# clock.net
KiCad netlist of a schematic drawn in EAGLE
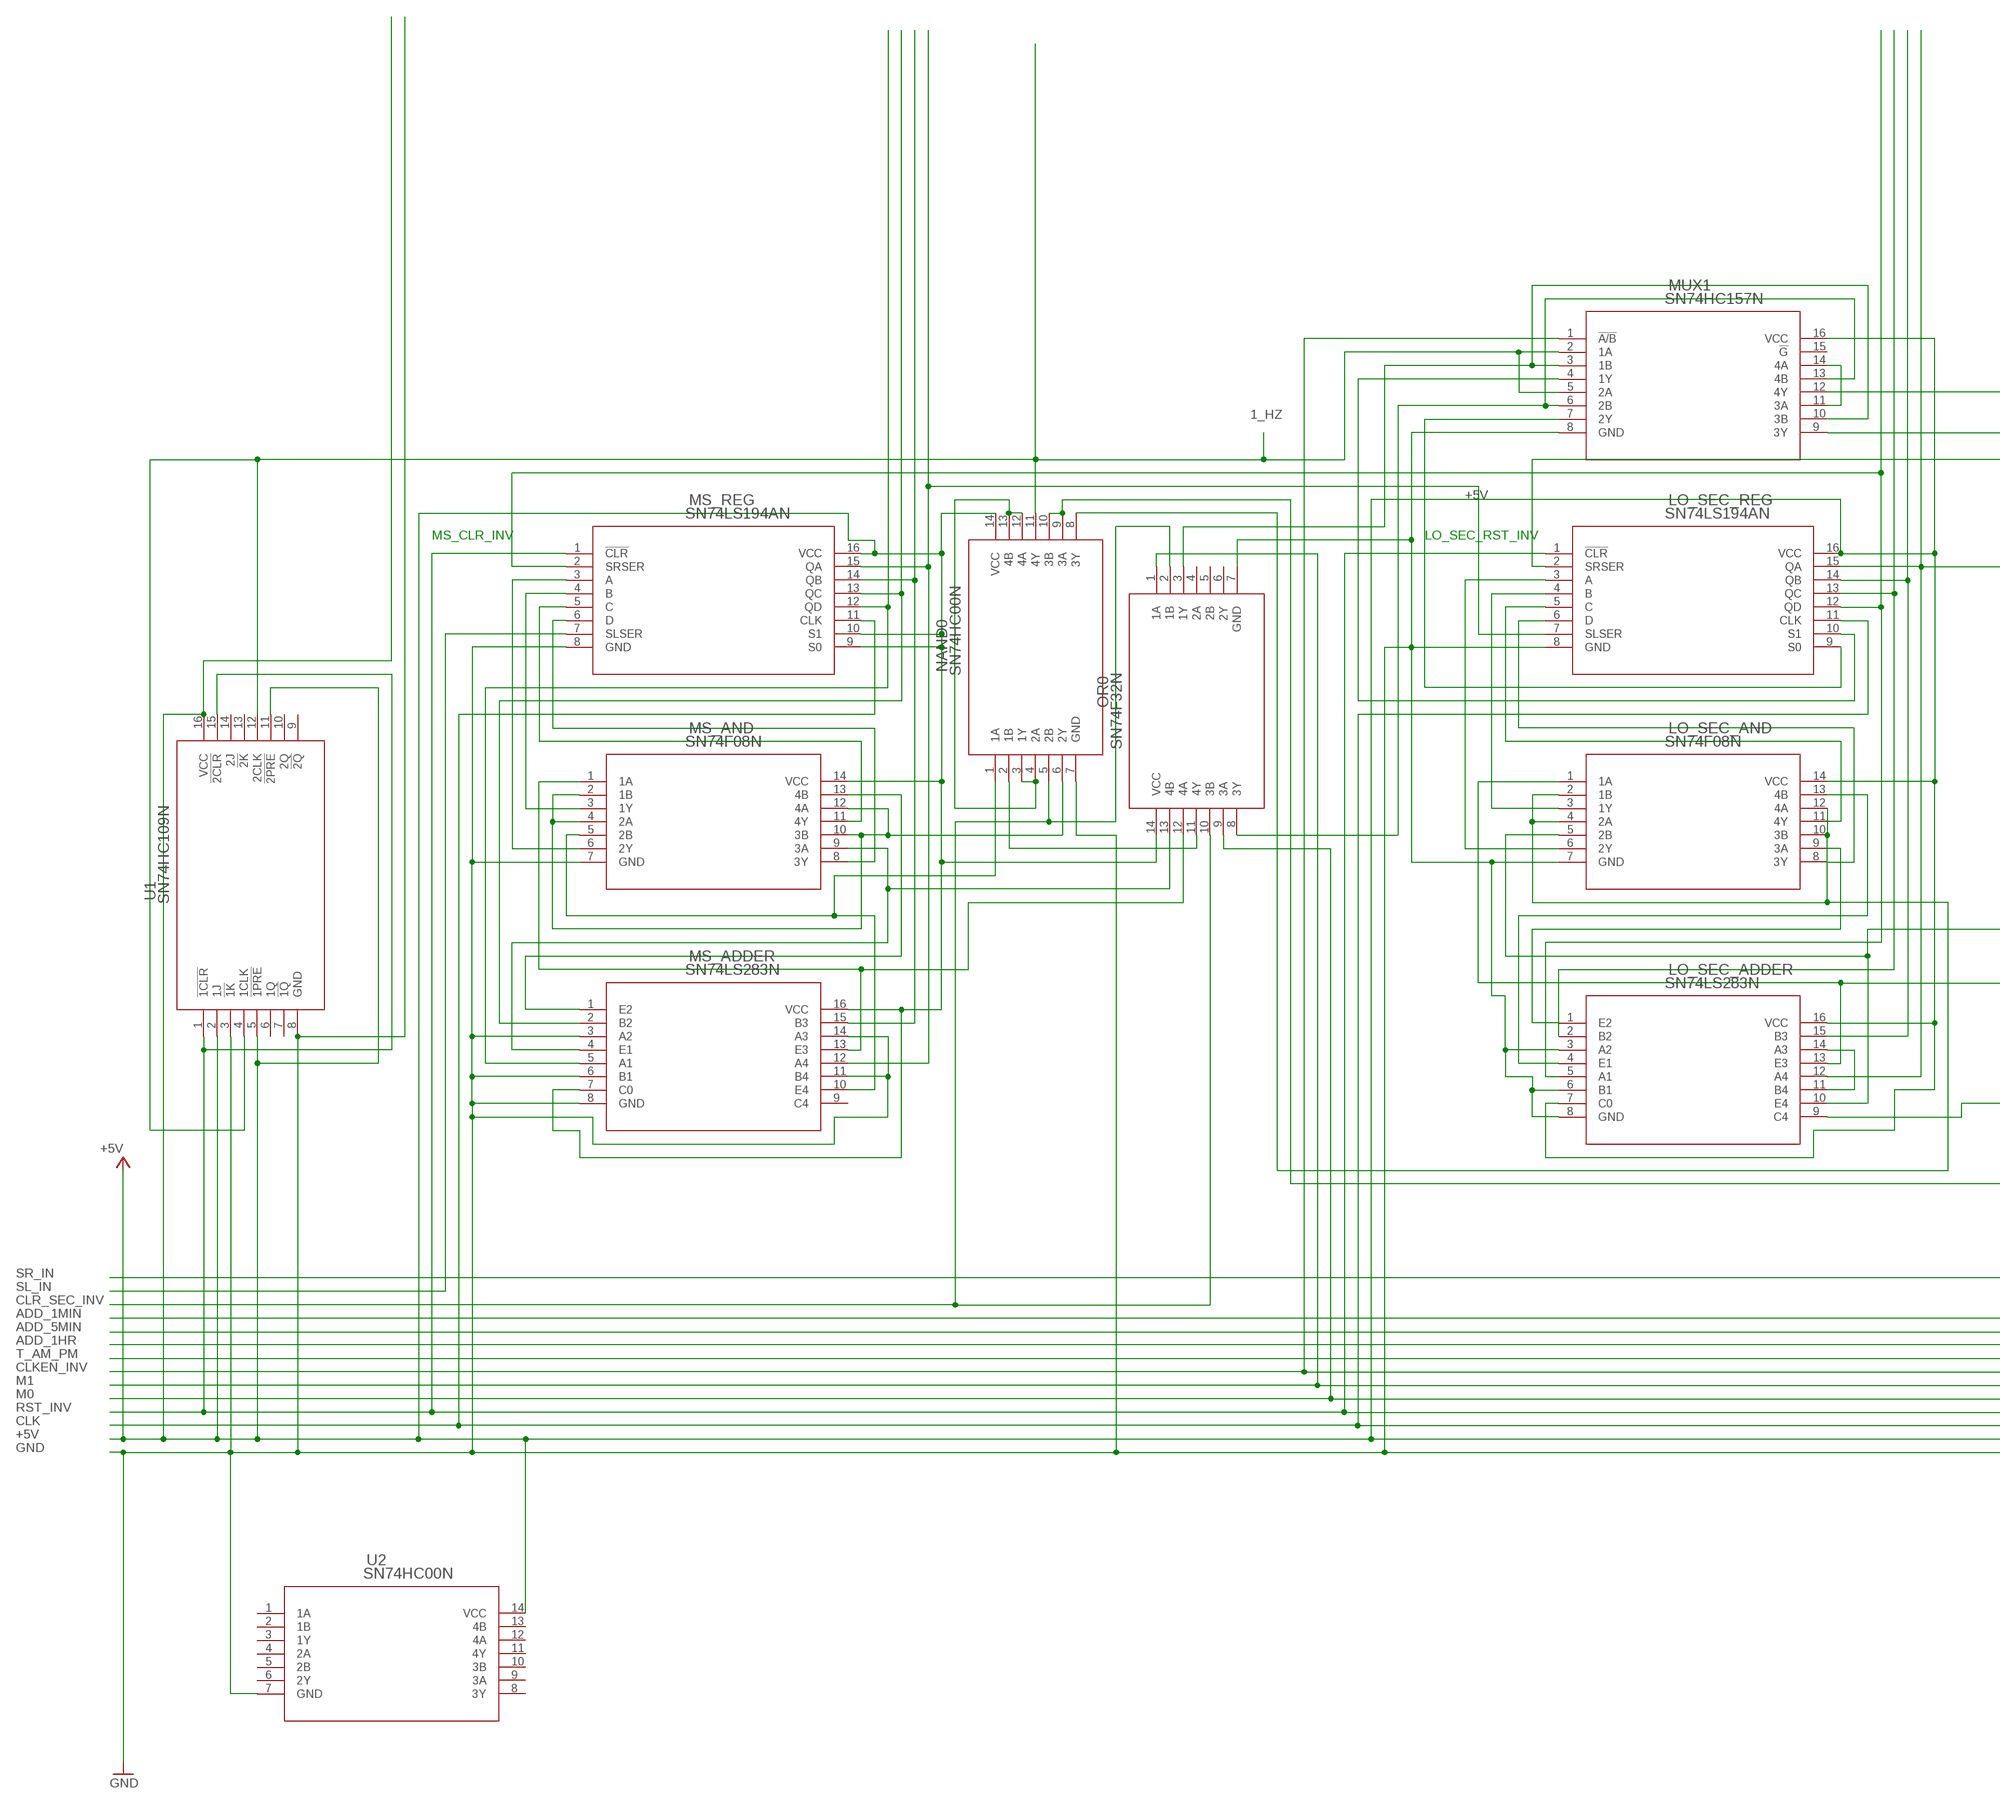
[diagram p0: schematic, sheet 1, part 1 of 3]
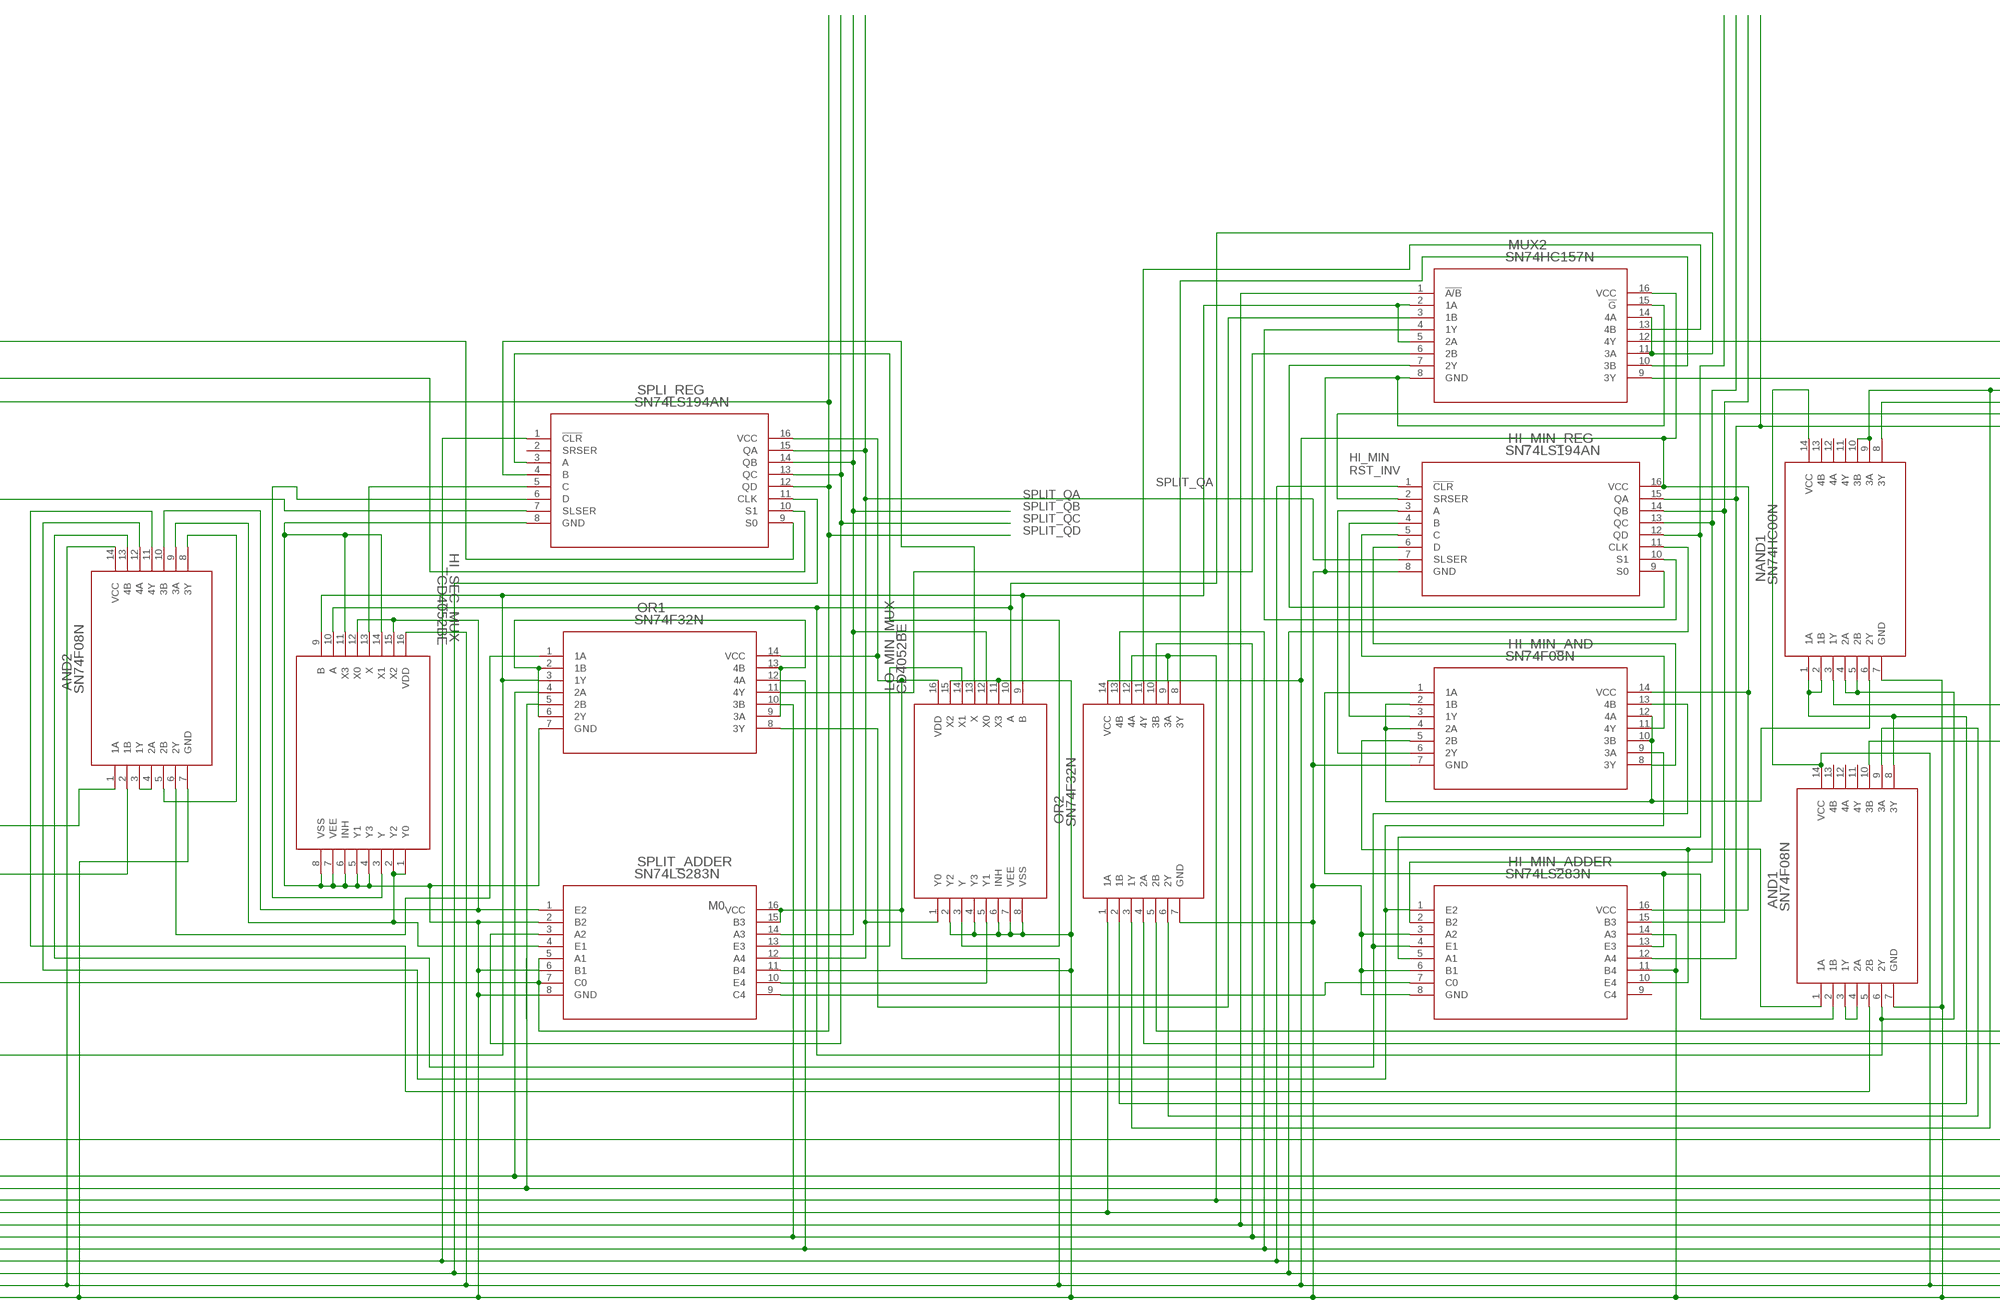
[diagram p1: schematic, sheet 1, part 2 of 3]
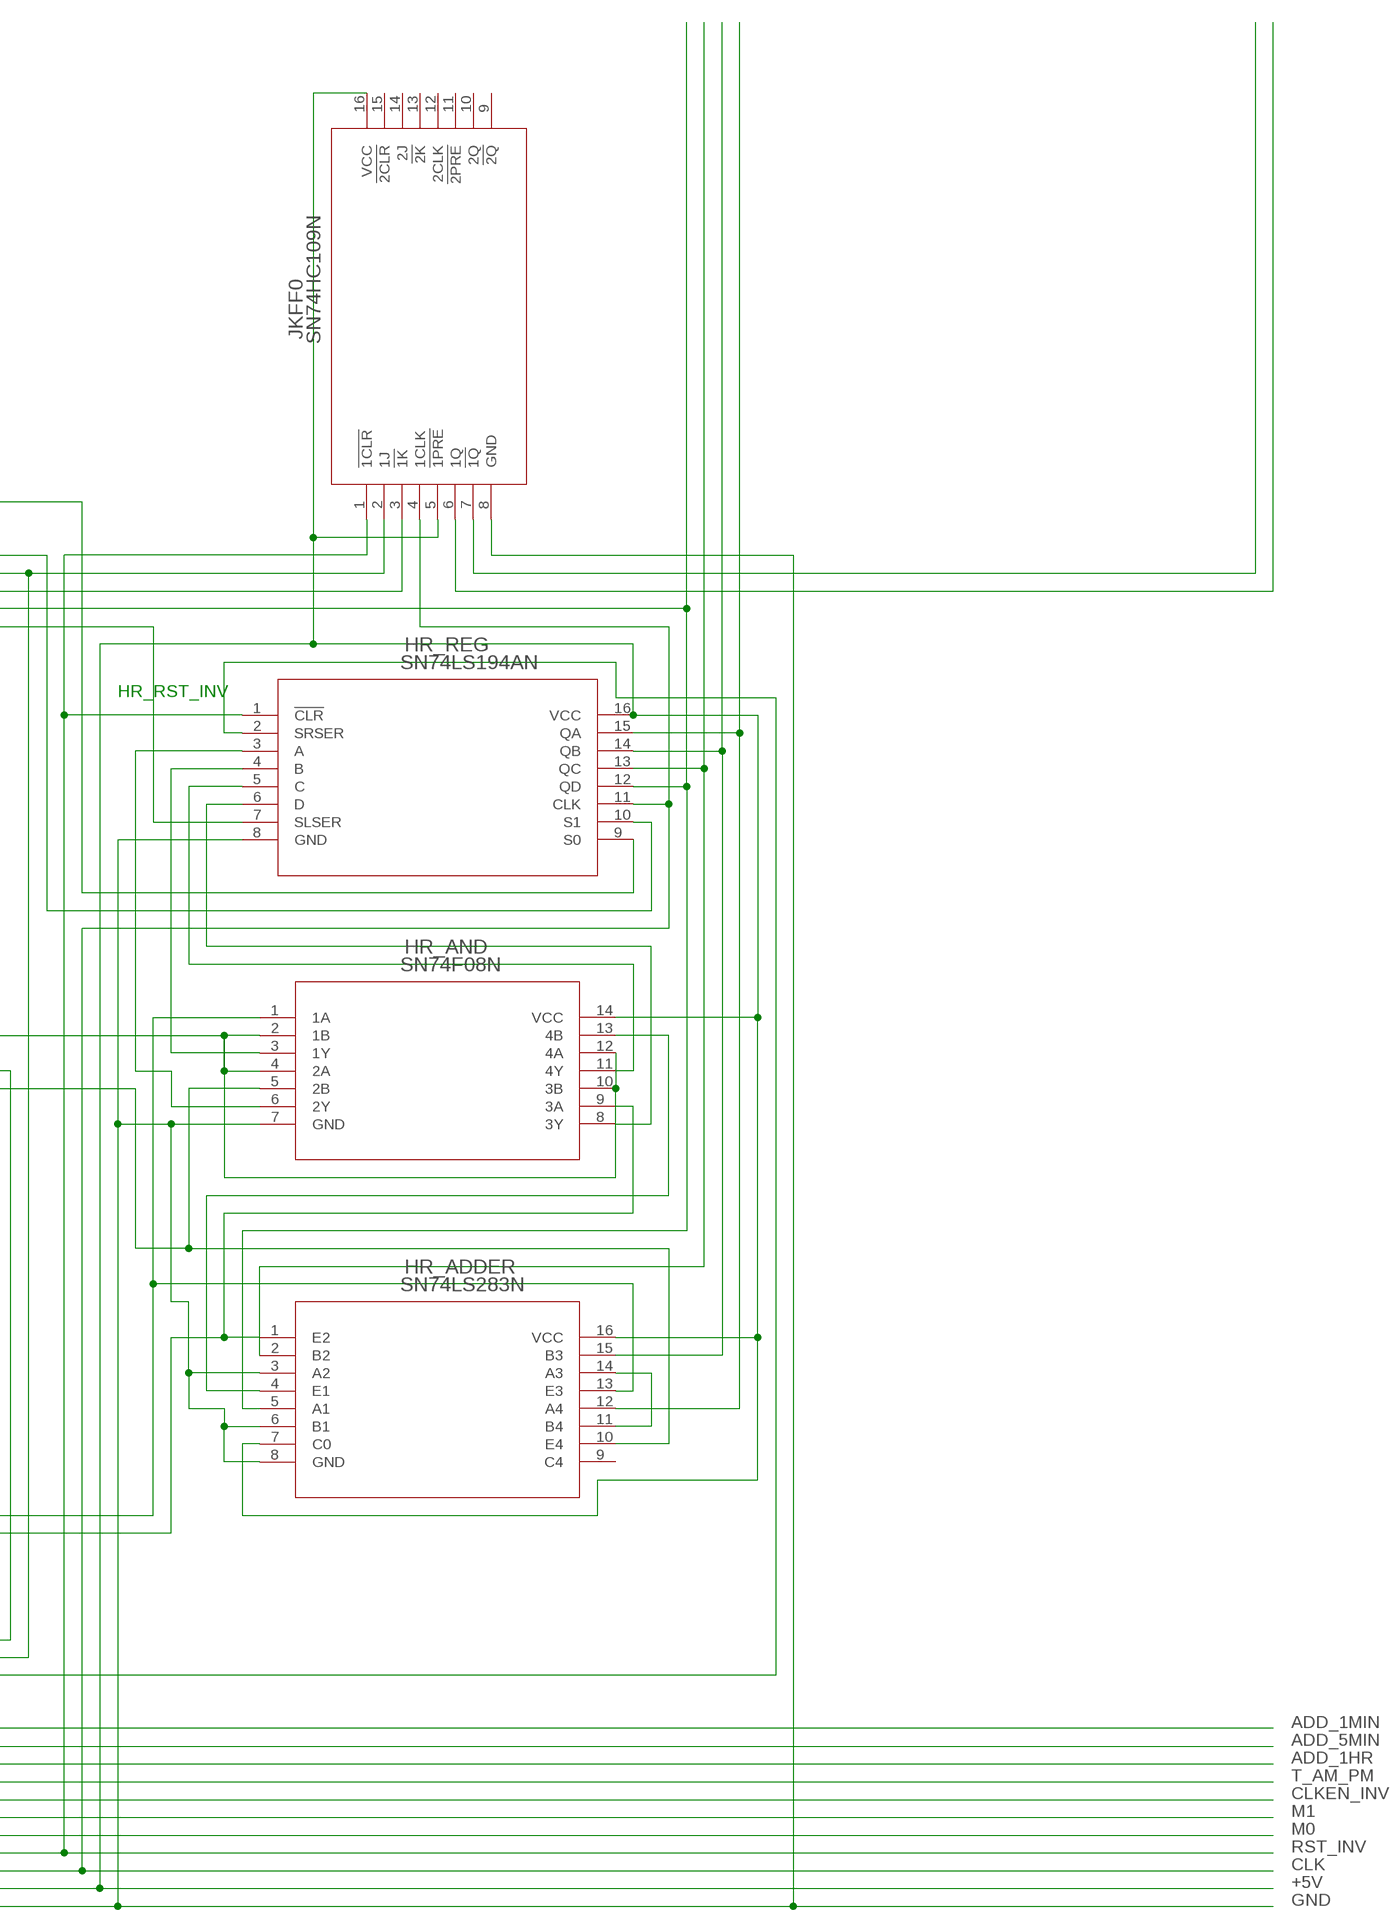
[diagram p2: schematic, sheet 1, part 3 of 3]

(export (version "E")
  (design (tool "Eeschema 10.0.6"))
  (components
    (comp (ref "AND1")
      (value "SN74F08N")
      (footprint "eagle-import:N14")
      (fields
        (field (name "GENERIC_PART_NUMBER") "SN74F08")
        (field (name "MANUFACTURER") "Texas Instruments")
      )
      (libsource (lib "eagle-import") (part "SN74F08N"))
    )
    (comp (ref "AND2")
      (value "SN74F08N")
      (footprint "eagle-import:N14")
      (fields
        (field (name "GENERIC_PART_NUMBER") "SN74F08")
        (field (name "MANUFACTURER") "Texas Instruments")
      )
      (libsource (lib "eagle-import") (part "SN74F08N"))
    )
    (comp (ref "HI_MIN_ADDER")
      (value "SN74LS283N")
      (footprint "eagle-import:N16")
      (fields
        (field (name "GENERIC_PART_NUMBER") "SN74LS283")
        (field (name "MANUFACTURER") "Texas Instruments")
      )
      (libsource (lib "eagle-import") (part "SN74LS283N"))
    )
    (comp (ref "HI_MIN_AND")
      (value "SN74F08N")
      (footprint "eagle-import:N14")
      (fields
        (field (name "GENERIC_PART_NUMBER") "SN74F08")
        (field (name "MANUFACTURER") "Texas Instruments")
      )
      (libsource (lib "eagle-import") (part "SN74F08N"))
    )
    (comp (ref "HI_MIN_REG")
      (value "SN74LS194AN")
      (footprint "eagle-import:N16")
      (fields
        (field (name "GENERIC_PART_NUMBER") "SN74LS194A")
        (field (name "MANUFACTURER") "Texas Instruments")
      )
      (libsource (lib "eagle-import") (part "SN74LS194AN"))
    )
    (comp (ref "HI_SEC_MUX")
      (value "CD4052BE")
      (footprint "eagle-import:N16")
      (fields
        (field (name "GENERIC_PART_NUMBER") "CD4052B")
        (field (name "MANUFACTURER") "Texas Instruments")
      )
      (libsource (lib "eagle-import") (part "CD4052BE"))
    )
    (comp (ref "HR_ADDER")
      (value "SN74LS283N")
      (footprint "eagle-import:N16")
      (fields
        (field (name "GENERIC_PART_NUMBER") "SN74LS283")
        (field (name "MANUFACTURER") "Texas Instruments")
      )
      (libsource (lib "eagle-import") (part "SN74LS283N"))
    )
    (comp (ref "HR_AND")
      (value "SN74F08N")
      (footprint "eagle-import:N14")
      (fields
        (field (name "GENERIC_PART_NUMBER") "SN74F08")
        (field (name "MANUFACTURER") "Texas Instruments")
      )
      (libsource (lib "eagle-import") (part "SN74F08N"))
    )
    (comp (ref "HR_REG")
      (value "SN74LS194AN")
      (footprint "eagle-import:N16")
      (fields
        (field (name "GENERIC_PART_NUMBER") "SN74LS194A")
        (field (name "MANUFACTURER") "Texas Instruments")
      )
      (libsource (lib "eagle-import") (part "SN74LS194AN"))
    )
    (comp (ref "JKFF0")
      (value "SN74HC109N")
      (footprint "eagle-import:N16")
      (fields
        (field (name "GENERIC_PART_NUMBER") "SN74HC109")
        (field (name "MANUFACTURER") "Texas Instruments")
      )
      (libsource (lib "eagle-import") (part "SN74HC109N"))
    )
    (comp (ref "LO_MIN_MUX")
      (value "CD4052BE")
      (footprint "eagle-import:N16")
      (fields
        (field (name "GENERIC_PART_NUMBER") "CD4052B")
        (field (name "MANUFACTURER") "Texas Instruments")
      )
      (libsource (lib "eagle-import") (part "CD4052BE"))
    )
    (comp (ref "LO_SEC_ADDER")
      (value "SN74LS283N")
      (footprint "eagle-import:N16")
      (fields
        (field (name "GENERIC_PART_NUMBER") "SN74LS283")
        (field (name "MANUFACTURER") "Texas Instruments")
      )
      (libsource (lib "eagle-import") (part "SN74LS283N"))
    )
    (comp (ref "LO_SEC_AND")
      (value "SN74F08N")
      (footprint "eagle-import:N14")
      (fields
        (field (name "GENERIC_PART_NUMBER") "SN74F08")
        (field (name "MANUFACTURER") "Texas Instruments")
      )
      (libsource (lib "eagle-import") (part "SN74F08N"))
    )
    (comp (ref "LO_SEC_REG")
      (value "SN74LS194AN")
      (footprint "eagle-import:N16")
      (fields
        (field (name "GENERIC_PART_NUMBER") "SN74LS194A")
        (field (name "MANUFACTURER") "Texas Instruments")
      )
      (libsource (lib "eagle-import") (part "SN74LS194AN"))
    )
    (comp (ref "MS_ADDER")
      (value "SN74LS283N")
      (footprint "eagle-import:N16")
      (fields
        (field (name "GENERIC_PART_NUMBER") "SN74LS283")
        (field (name "MANUFACTURER") "Texas Instruments")
      )
      (libsource (lib "eagle-import") (part "SN74LS283N"))
    )
    (comp (ref "MS_AND")
      (value "SN74F08N")
      (footprint "eagle-import:N14")
      (fields
        (field (name "GENERIC_PART_NUMBER") "SN74F08")
        (field (name "MANUFACTURER") "Texas Instruments")
      )
      (libsource (lib "eagle-import") (part "SN74F08N"))
    )
    (comp (ref "MS_REG")
      (value "SN74LS194AN")
      (footprint "eagle-import:N16")
      (fields
        (field (name "GENERIC_PART_NUMBER") "SN74LS194A")
        (field (name "MANUFACTURER") "Texas Instruments")
      )
      (libsource (lib "eagle-import") (part "SN74LS194AN"))
    )
    (comp (ref "MUX1")
      (value "SN74HC157N")
      (footprint "eagle-import:N16")
      (fields
        (field (name "GENERIC_PART_NUMBER") "SN74HC157")
        (field (name "MANUFACTURER") "Texas Instruments")
      )
      (libsource (lib "eagle-import") (part "SN74HC157N"))
    )
    (comp (ref "MUX2")
      (value "SN74HC157N")
      (footprint "eagle-import:N16")
      (fields
        (field (name "GENERIC_PART_NUMBER") "SN74HC157")
        (field (name "MANUFACTURER") "Texas Instruments")
      )
      (libsource (lib "eagle-import") (part "SN74HC157N"))
    )
    (comp (ref "NAND0")
      (value "SN74HC00N")
      (footprint "eagle-import:N14")
      (fields
        (field (name "GENERIC_PART_NUMBER") "SN74HC00")
        (field (name "MANUFACTURER") "Texas Instruments")
      )
      (libsource (lib "eagle-import") (part "SN74HC00N"))
    )
    (comp (ref "NAND1")
      (value "SN74HC00N")
      (footprint "eagle-import:N14")
      (fields
        (field (name "GENERIC_PART_NUMBER") "SN74HC00")
        (field (name "MANUFACTURER") "Texas Instruments")
      )
      (libsource (lib "eagle-import") (part "SN74HC00N"))
    )
    (comp (ref "OR0")
      (value "SN74F32N")
      (footprint "eagle-import:N14")
      (fields
        (field (name "GENERIC_PART_NUMBER") "SN74F32")
        (field (name "MANUFACTURER") "Texas Instruments")
      )
      (libsource (lib "eagle-import") (part "SN74F32N"))
    )
    (comp (ref "OR1")
      (value "SN74F32N")
      (footprint "eagle-import:N14")
      (fields
        (field (name "GENERIC_PART_NUMBER") "SN74F32")
        (field (name "MANUFACTURER") "Texas Instruments")
      )
      (libsource (lib "eagle-import") (part "SN74F32N"))
    )
    (comp (ref "OR2")
      (value "SN74F32N")
      (footprint "eagle-import:N14")
      (fields
        (field (name "GENERIC_PART_NUMBER") "SN74F32")
        (field (name "MANUFACTURER") "Texas Instruments")
      )
      (libsource (lib "eagle-import") (part "SN74F32N"))
    )
    (comp (ref "SPLIT_ADDER")
      (value "SN74LS283N")
      (footprint "eagle-import:N16")
      (fields
        (field (name "GENERIC_PART_NUMBER") "SN74LS283")
        (field (name "MANUFACTURER") "Texas Instruments")
      )
      (libsource (lib "eagle-import") (part "SN74LS283N"))
    )
    (comp (ref "SPLI_REG")
      (value "SN74LS194AN")
      (footprint "eagle-import:N16")
      (fields
        (field (name "GENERIC_PART_NUMBER") "SN74LS194A")
        (field (name "MANUFACTURER") "Texas Instruments")
      )
      (libsource (lib "eagle-import") (part "SN74LS194AN"))
    )
    (comp (ref "U1")
      (value "SN74HC109N")
      (footprint "eagle-import:N16")
      (fields
        (field (name "GENERIC_PART_NUMBER") "SN74HC109")
        (field (name "MANUFACTURER") "Texas Instruments")
      )
      (libsource (lib "eagle-import") (part "SN74HC109N"))
    )
    (comp (ref "U2")
      (value "SN74HC00N")
      (footprint "eagle-import:N14")
      (fields
        (field (name "GENERIC_PART_NUMBER") "SN74HC00")
        (field (name "MANUFACTURER") "Texas Instruments")
      )
      (libsource (lib "eagle-import") (part "SN74HC00N"))
    )
  )
  (nets
    (net (code "1") (name "+5V") (class "Default")
      (node (ref "AND1") (pin "14") (pinfunction "VCC_14") (pintype "power_in"))
      (node (ref "AND2") (pin "14") (pinfunction "VCC_14") (pintype "power_in"))
      (node (ref "HI_MIN_ADDER") (pin "16") (pinfunction "VCC_16") (pintype "power_in"))
      (node (ref "HI_MIN_AND") (pin "14") (pinfunction "VCC_14") (pintype "power_in"))
      (node (ref "HI_MIN_REG") (pin "16") (pinfunction "VCC_16") (pintype "power_in"))
      (node (ref "HI_SEC_MUX") (pin "16") (pinfunction "VDD_16") (pintype "power_in"))
      (node (ref "HR_ADDER") (pin "16") (pinfunction "VCC_16") (pintype "power_in"))
      (node (ref "HR_ADDER") (pin "7") (pinfunction "C0_7") (pintype "input"))
      (node (ref "HR_AND") (pin "14") (pinfunction "VCC_14") (pintype "power_in"))
      (node (ref "HR_REG") (pin "16") (pinfunction "VCC_16") (pintype "power_in"))
      (node (ref "JKFF0") (pin "16") (pinfunction "VCC_16") (pintype "power_in"))
      (node (ref "JKFF0") (pin "5") (pinfunction "~{1PRE}_5") (pintype "input"))
      (node (ref "LO_MIN_MUX") (pin "16") (pinfunction "VDD_16") (pintype "power_in"))
      (node (ref "LO_SEC_ADDER") (pin "16") (pinfunction "VCC_16") (pintype "power_in"))
      (node (ref "LO_SEC_ADDER") (pin "7") (pinfunction "C0_7") (pintype "input"))
      (node (ref "LO_SEC_AND") (pin "14") (pinfunction "VCC_14") (pintype "power_in"))
      (node (ref "LO_SEC_REG") (pin "16") (pinfunction "VCC_16") (pintype "power_in"))
      (node (ref "MS_ADDER") (pin "16") (pinfunction "VCC_16") (pintype "power_in"))
      (node (ref "MS_ADDER") (pin "7") (pinfunction "C0_7") (pintype "input"))
      (node (ref "MS_AND") (pin "14") (pinfunction "VCC_14") (pintype "power_in"))
      (node (ref "MS_REG") (pin "10") (pinfunction "S1_10") (pintype "input"))
      (node (ref "MS_REG") (pin "16") (pinfunction "VCC_16") (pintype "power_in"))
      (node (ref "MS_REG") (pin "9") (pinfunction "S0_9") (pintype "input"))
      (node (ref "MUX1") (pin "16") (pinfunction "VCC_16") (pintype "power_in"))
      (node (ref "MUX2") (pin "16") (pinfunction "VCC_16") (pintype "power_in"))
      (node (ref "NAND0") (pin "14") (pinfunction "VCC_14") (pintype "power_in"))
      (node (ref "NAND1") (pin "14") (pinfunction "VCC_14") (pintype "power_in"))
      (node (ref "OR0") (pin "14") (pinfunction "VCC_14") (pintype "power_in"))
      (node (ref "OR1") (pin "14") (pinfunction "VCC_14") (pintype "power_in"))
      (node (ref "OR2") (pin "14") (pinfunction "VCC_14") (pintype "power_in"))
      (node (ref "SPLIT_ADDER") (pin "15") (pinfunction "B3_15") (pintype "input"))
      (node (ref "SPLIT_ADDER") (pin "16") (pinfunction "VCC_16") (pintype "power_in"))
      (node (ref "SPLI_REG") (pin "16") (pinfunction "VCC_16") (pintype "power_in"))
      (node (ref "U1") (pin "11") (pinfunction "~{2PRE}_11") (pintype "input"))
      (node (ref "U1") (pin "16") (pinfunction "VCC_16") (pintype "power_in"))
      (node (ref "U1") (pin "2") (pinfunction "1J_2") (pintype "input"))
      (node (ref "U1") (pin "5") (pinfunction "~{1PRE}_5") (pintype "input"))
      (node (ref "U2") (pin "14") (pinfunction "VCC_14") (pintype "power_in"))
    )
    (net (code "2") (name "/1_HZ") (class "Default")
      (node (ref "MUX1") (pin "2") (pinfunction "1A_2") (pintype "input"))
      (node (ref "MUX1") (pin "5") (pinfunction "2A_5") (pintype "input"))
      (node (ref "NAND0") (pin "11") (pinfunction "4Y_11") (pintype "output"))
      (node (ref "U1") (pin "12") (pinfunction "2CLK_12") (pintype "input"))
      (node (ref "U1") (pin "4") (pinfunction "1CLK_4") (pintype "input"))
    )
    (net (code "3") (name "/ADD_1HR") (class "Default")
      (node (ref "OR2") (pin "12") (pinfunction "4A_12") (pintype "input"))
      (node (ref "OR2") (pin "9") (pinfunction "3A_9") (pintype "input"))
    )
    (net (code "4") (name "/ADD_1MIN") (class "Default")
      (node (ref "OR1") (pin "4") (pinfunction "2A_4") (pintype "input"))
    )
    (net (code "5") (name "/ADD_5MIN") (class "Default")
      (node (ref "OR1") (pin "5") (pinfunction "2B_5") (pintype "input"))
    )
    (net (code "6") (name "/CLK") (class "Default")
      (node (ref "HI_MIN_REG") (pin "11") (pinfunction "CLK_11") (pintype "input"))
      (node (ref "HR_REG") (pin "11") (pinfunction "CLK_11") (pintype "input"))
      (node (ref "JKFF0") (pin "4") (pinfunction "1CLK_4") (pintype "input"))
      (node (ref "LO_SEC_REG") (pin "11") (pinfunction "CLK_11") (pintype "input"))
      (node (ref "MS_REG") (pin "11") (pinfunction "CLK_11") (pintype "input"))
      (node (ref "SPLI_REG") (pin "11") (pinfunction "CLK_11") (pintype "input"))
    )
    (net (code "7") (name "/CLKEN_INV") (class "Default")
      (node (ref "MUX1") (pin "1") (pinfunction "~{A/B}_1") (pintype "input"))
      (node (ref "MUX2") (pin "1") (pinfunction "~{A/B}_1") (pintype "input"))
    )
    (net (code "8") (name "/CLR_SEC_INV") (class "Default")
      (node (ref "NAND0") (pin "5") (pinfunction "2B_5") (pintype "input"))
      (node (ref "OR0") (pin "10") (pinfunction "3B_10") (pintype "input"))
      (node (ref "OR0") (pin "2") (pinfunction "1B_2") (pintype "input"))
    )
    (net (code "9") (name "/M0") (class "Default")
      (node (ref "OR0") (pin "9") (pinfunction "3A_9") (pintype "input"))
      (node (ref "OR1") (pin "12") (pinfunction "4A_12") (pintype "input"))
      (node (ref "OR2") (pin "13") (pinfunction "4B_13") (pintype "input"))
    )
    (net (code "10") (name "/M1") (class "Default")
      (node (ref "OR0") (pin "1") (pinfunction "1A_1") (pintype "input"))
      (node (ref "OR1") (pin "10") (pinfunction "3B_10") (pintype "input"))
      (node (ref "OR2") (pin "10") (pinfunction "3B_10") (pintype "input"))
    )
    (net (code "11") (name "/RST_INV") (class "Default")
      (node (ref "HI_MIN_REG") (pin "1") (pinfunction "~{CLR}_1") (pintype "input"))
      (node (ref "HR_REG") (pin "1") (pinfunction "~{CLR}_1") (pintype "input"))
      (node (ref "JKFF0") (pin "1") (pinfunction "~{1CLR}_1") (pintype "input"))
      (node (ref "LO_SEC_REG") (pin "1") (pinfunction "~{CLR}_1") (pintype "input"))
      (node (ref "MS_REG") (pin "1") (pinfunction "~{CLR}_1") (pintype "input"))
      (node (ref "SPLI_REG") (pin "1") (pinfunction "~{CLR}_1") (pintype "input"))
      (node (ref "U1") (pin "1") (pinfunction "~{1CLR}_1") (pintype "input"))
      (node (ref "U1") (pin "15") (pinfunction "~{2CLR}_15") (pintype "input"))
    )
    (net (code "12") (name "/SL_IN") (class "Default")
      (node (ref "MS_REG") (pin "7") (pinfunction "SLSER_7") (pintype "input"))
    )
    (net (code "13") (name "/SPLIT_QA") (class "Default")
      (node (ref "HI_MIN_REG") (pin "7") (pinfunction "SLSER_7") (pintype "input"))
      (node (ref "LO_MIN_MUX") (pin "1") (pinfunction "Y0_1") (pintype "bidirectional"))
      (node (ref "SPLIT_ADDER") (pin "12") (pinfunction "A4_12") (pintype "input"))
      (node (ref "SPLI_REG") (pin "15") (pinfunction "QA_15") (pintype "output"))
    )
    (net (code "14") (name "/SPLIT_QB") (class "Default")
      (node (ref "LO_MIN_MUX") (pin "12") (pinfunction "X0_12") (pintype "bidirectional"))
      (node (ref "SPLIT_ADDER") (pin "14") (pinfunction "A3_14") (pintype "input"))
      (node (ref "SPLI_REG") (pin "14") (pinfunction "QB_14") (pintype "output"))
    )
    (net (code "15") (name "/SPLIT_QC") (class "Default")
      (node (ref "SPLIT_ADDER") (pin "3") (pinfunction "A2_3") (pintype "input"))
      (node (ref "SPLI_REG") (pin "13") (pinfunction "QC_13") (pintype "output"))
    )
    (net (code "16") (name "/SPLIT_QD") (class "Default")
      (node (ref "LO_SEC_ADDER") (pin "9") (pinfunction "C4_9") (pintype "input"))
      (node (ref "LO_SEC_REG") (pin "2") (pinfunction "SRSER_2") (pintype "input"))
      (node (ref "SPLIT_ADDER") (pin "5") (pinfunction "A1_5") (pintype "input"))
      (node (ref "SPLIT_ADDER") (pin "7") (pinfunction "C0_7") (pintype "input"))
      (node (ref "SPLI_REG") (pin "12") (pinfunction "QD_12") (pintype "output"))
    )
    (net (code "17") (name "/SR_IN") (class "Default")
      (node (ref "HR_REG") (pin "2") (pinfunction "SRSER_2") (pintype "input"))
    )
    (net (code "18") (name "/T_AM_PM") (class "Default")
      (node (ref "OR2") (pin "1") (pinfunction "1A_1") (pintype "input"))
    )
    (net (code "19") (name "GND") (class "Default")
      (node (ref "AND1") (pin "7") (pinfunction "GND_7") (pintype "power_in"))
      (node (ref "AND2") (pin "7") (pinfunction "GND_7") (pintype "power_in"))
      (node (ref "HI_MIN_ADDER") (pin "11") (pinfunction "B4_11") (pintype "input"))
      (node (ref "HI_MIN_ADDER") (pin "14") (pinfunction "A3_14") (pintype "input"))
      (node (ref "HI_MIN_ADDER") (pin "3") (pinfunction "A2_3") (pintype "input"))
      (node (ref "HI_MIN_ADDER") (pin "6") (pinfunction "B1_6") (pintype "input"))
      (node (ref "HI_MIN_ADDER") (pin "8") (pinfunction "GND_8") (pintype "power_in"))
      (node (ref "HI_MIN_AND") (pin "7") (pinfunction "GND_7") (pintype "power_in"))
      (node (ref "HI_MIN_REG") (pin "8") (pinfunction "GND_8") (pintype "power_in"))
      (node (ref "HI_SEC_MUX") (pin "11") (pinfunction "X3_11") (pintype "bidirectional"))
      (node (ref "HI_SEC_MUX") (pin "14") (pinfunction "X1_14") (pintype "bidirectional"))
      (node (ref "HI_SEC_MUX") (pin "4") (pinfunction "Y3_4") (pintype "bidirectional"))
      (node (ref "HI_SEC_MUX") (pin "5") (pinfunction "Y1_5") (pintype "bidirectional"))
      (node (ref "HI_SEC_MUX") (pin "6") (pinfunction "INH_6") (pintype "passive"))
      (node (ref "HI_SEC_MUX") (pin "7") (pinfunction "VEE_7") (pintype "power_in"))
      (node (ref "HI_SEC_MUX") (pin "8") (pinfunction "VSS_8") (pintype "power_in"))
      (node (ref "HR_ADDER") (pin "3") (pinfunction "A2_3") (pintype "input"))
      (node (ref "HR_ADDER") (pin "6") (pinfunction "B1_6") (pintype "input"))
      (node (ref "HR_ADDER") (pin "8") (pinfunction "GND_8") (pintype "power_in"))
      (node (ref "HR_AND") (pin "7") (pinfunction "GND_7") (pintype "power_in"))
      (node (ref "HR_REG") (pin "8") (pinfunction "GND_8") (pintype "power_in"))
      (node (ref "JKFF0") (pin "8") (pinfunction "GND_8") (pintype "power_in"))
      (node (ref "LO_MIN_MUX") (pin "11") (pinfunction "X3_11") (pintype "bidirectional"))
      (node (ref "LO_MIN_MUX") (pin "15") (pinfunction "X2_15") (pintype "bidirectional"))
      (node (ref "LO_MIN_MUX") (pin "2") (pinfunction "Y2_2") (pintype "bidirectional"))
      (node (ref "LO_MIN_MUX") (pin "4") (pinfunction "Y3_4") (pintype "bidirectional"))
      (node (ref "LO_MIN_MUX") (pin "6") (pinfunction "INH_6") (pintype "passive"))
      (node (ref "LO_MIN_MUX") (pin "7") (pinfunction "VEE_7") (pintype "power_in"))
      (node (ref "LO_MIN_MUX") (pin "8") (pinfunction "VSS_8") (pintype "power_in"))
      (node (ref "LO_SEC_ADDER") (pin "3") (pinfunction "A2_3") (pintype "input"))
      (node (ref "LO_SEC_ADDER") (pin "6") (pinfunction "B1_6") (pintype "input"))
      (node (ref "LO_SEC_ADDER") (pin "8") (pinfunction "GND_8") (pintype "power_in"))
      (node (ref "LO_SEC_AND") (pin "7") (pinfunction "GND_7") (pintype "power_in"))
      (node (ref "LO_SEC_REG") (pin "8") (pinfunction "GND_8") (pintype "power_in"))
      (node (ref "MS_ADDER") (pin "11") (pinfunction "B4_11") (pintype "input"))
      (node (ref "MS_ADDER") (pin "14") (pinfunction "A3_14") (pintype "input"))
      (node (ref "MS_ADDER") (pin "3") (pinfunction "A2_3") (pintype "input"))
      (node (ref "MS_ADDER") (pin "6") (pinfunction "B1_6") (pintype "input"))
      (node (ref "MS_ADDER") (pin "8") (pinfunction "GND_8") (pintype "power_in"))
      (node (ref "MS_AND") (pin "7") (pinfunction "GND_7") (pintype "power_in"))
      (node (ref "MS_REG") (pin "8") (pinfunction "GND_8") (pintype "power_in"))
      (node (ref "MUX1") (pin "8") (pinfunction "GND_8") (pintype "power_in"))
      (node (ref "MUX2") (pin "15") (pinfunction "~{G}_15") (pintype "input"))
      (node (ref "MUX2") (pin "8") (pinfunction "GND_8") (pintype "power_in"))
      (node (ref "NAND0") (pin "7") (pinfunction "GND_7") (pintype "power_in"))
      (node (ref "NAND1") (pin "7") (pinfunction "GND_7") (pintype "power_in"))
      (node (ref "OR0") (pin "7") (pinfunction "GND_7") (pintype "power_in"))
      (node (ref "OR1") (pin "7") (pinfunction "GND_7") (pintype "power_in"))
      (node (ref "OR2") (pin "7") (pinfunction "GND_7") (pintype "power_in"))
      (node (ref "SPLIT_ADDER") (pin "11") (pinfunction "B4_11") (pintype "input"))
      (node (ref "SPLIT_ADDER") (pin "2") (pinfunction "B2_2") (pintype "input"))
      (node (ref "SPLIT_ADDER") (pin "6") (pinfunction "B1_6") (pintype "input"))
      (node (ref "SPLIT_ADDER") (pin "8") (pinfunction "GND_8") (pintype "power_in"))
      (node (ref "SPLI_REG") (pin "8") (pinfunction "GND_8") (pintype "power_in"))
      (node (ref "U1") (pin "3") (pinfunction "~{1K}_3") (pintype "input"))
      (node (ref "U1") (pin "8") (pinfunction "GND_8") (pintype "power_in"))
      (node (ref "U2") (pin "7") (pinfunction "GND_7") (pintype "power_in"))
    )
    (net (code "20") (name "Net-(AND1-1A)") (class "Default")
      (node (ref "AND1") (pin "1") (pinfunction "1A_1") (pintype "input"))
      (node (ref "HI_MIN_ADDER") (pin "10") (pinfunction "E4_10") (pintype "output"))
      (node (ref "HI_MIN_AND") (pin "5") (pinfunction "2B_5") (pintype "input"))
    )
    (net (code "21") (name "Net-(AND1-1B)") (class "Default")
      (node (ref "AND1") (pin "2") (pinfunction "1B_2") (pintype "input"))
      (node (ref "HI_MIN_ADDER") (pin "13") (pinfunction "E3_13") (pintype "output"))
      (node (ref "HI_MIN_AND") (pin "1") (pinfunction "1A_1") (pintype "input"))
    )
    (net (code "22") (name "Net-(AND1-1Y)") (class "Default")
      (node (ref "AND1") (pin "3") (pinfunction "1Y_3") (pintype "output"))
      (node (ref "AND1") (pin "4") (pinfunction "2A_4") (pintype "input"))
    )
    (net (code "23") (name "Net-(AND1-2B)") (class "Default")
      (node (ref "AND1") (pin "5") (pinfunction "2B_5") (pintype "input"))
      (node (ref "AND2") (pin "11") (pinfunction "4Y_11") (pintype "output"))
    )
    (net (code "24") (name "Net-(AND1-2Y)") (class "Default")
      (node (ref "AND1") (pin "6") (pinfunction "2Y_6") (pintype "output"))
      (node (ref "HI_SEC_MUX") (pin "10") (pinfunction "A_10") (pintype "passive"))
      (node (ref "LO_MIN_MUX") (pin "10") (pinfunction "A_10") (pintype "passive"))
      (node (ref "MUX2") (pin "11") (pinfunction "3A_11") (pintype "input"))
      (node (ref "MUX2") (pin "14") (pinfunction "4A_14") (pintype "input"))
      (node (ref "NAND1") (pin "4") (pinfunction "2A_4") (pintype "input"))
      (node (ref "NAND1") (pin "5") (pinfunction "2B_5") (pintype "input"))
    )
    (net (code "25") (name "Net-(AND1-3A)") (class "Default")
      (node (ref "AND1") (pin "9") (pinfunction "3A_9") (pintype "input"))
      (node (ref "OR2") (pin "6") (pinfunction "2Y_6") (pintype "output"))
    )
    (net (code "26") (name "Net-(AND1-3B)") (class "Default")
      (node (ref "AND1") (pin "10") (pinfunction "3B_10") (pintype "input"))
      (node (ref "HR_ADDER") (pin "10") (pinfunction "E4_10") (pintype "output"))
      (node (ref "HR_AND") (pin "5") (pinfunction "2B_5") (pintype "input"))
    )
    (net (code "27") (name "Net-(AND1-3Y)") (class "Default")
      (node (ref "AND1") (pin "8") (pinfunction "3Y_8") (pintype "output"))
      (node (ref "NAND1") (pin "1") (pinfunction "1A_1") (pintype "input"))
      (node (ref "NAND1") (pin "2") (pinfunction "1B_2") (pintype "input"))
      (node (ref "OR2") (pin "2") (pinfunction "1B_2") (pintype "input"))
    )
    (net (code "28") (name "Net-(AND2-1A)") (class "Default")
      (node (ref "AND2") (pin "1") (pinfunction "1A_1") (pintype "input"))
      (node (ref "LO_SEC_ADDER") (pin "10") (pinfunction "E4_10") (pintype "output"))
      (node (ref "LO_SEC_AND") (pin "5") (pinfunction "2B_5") (pintype "input"))
    )
    (net (code "29") (name "Net-(AND2-1B)") (class "Default")
      (node (ref "AND2") (pin "2") (pinfunction "1B_2") (pintype "input"))
      (node (ref "LO_SEC_ADDER") (pin "13") (pinfunction "E3_13") (pintype "output"))
      (node (ref "LO_SEC_AND") (pin "1") (pinfunction "1A_1") (pintype "input"))
    )
    (net (code "30") (name "Net-(AND2-1Y)") (class "Default")
      (node (ref "AND2") (pin "3") (pinfunction "1Y_3") (pintype "output"))
      (node (ref "AND2") (pin "4") (pinfunction "2A_4") (pintype "input"))
    )
    (net (code "31") (name "Net-(AND2-2B)") (class "Default")
      (node (ref "AND2") (pin "5") (pinfunction "2B_5") (pintype "input"))
      (node (ref "AND2") (pin "8") (pinfunction "3Y_8") (pintype "output"))
    )
    (net (code "32") (name "Net-(AND2-2Y)") (class "Default")
      (node (ref "AND2") (pin "6") (pinfunction "2Y_6") (pintype "output"))
      (node (ref "OR1") (pin "1") (pinfunction "1A_1") (pintype "input"))
    )
    (net (code "33") (name "Net-(AND2-3A)") (class "Default")
      (node (ref "AND2") (pin "9") (pinfunction "3A_9") (pintype "input"))
      (node (ref "HI_SEC_MUX") (pin "1") (pinfunction "Y0_1") (pintype "bidirectional"))
      (node (ref "HI_SEC_MUX") (pin "2") (pinfunction "Y2_2") (pintype "bidirectional"))
      (node (ref "SPLIT_ADDER") (pin "4") (pinfunction "E1_4") (pintype "output"))
    )
    (net (code "34") (name "Net-(AND2-3B)") (class "Default")
      (node (ref "AND2") (pin "10") (pinfunction "3B_10") (pintype "input"))
      (node (ref "HI_SEC_MUX") (pin "12") (pinfunction "X0_12") (pintype "bidirectional"))
      (node (ref "HI_SEC_MUX") (pin "15") (pinfunction "X2_15") (pintype "bidirectional"))
      (node (ref "SPLIT_ADDER") (pin "1") (pinfunction "E2_1") (pintype "output"))
    )
    (net (code "35") (name "Net-(AND2-4A)") (class "Default")
      (node (ref "AND2") (pin "12") (pinfunction "4A_12") (pintype "input"))
      (node (ref "HI_MIN_ADDER") (pin "1") (pinfunction "E2_1") (pintype "output"))
      (node (ref "HI_MIN_AND") (pin "9") (pinfunction "3A_9") (pintype "input"))
    )
    (net (code "36") (name "Net-(AND2-4B)") (class "Default")
      (node (ref "AND2") (pin "13") (pinfunction "4B_13") (pintype "input"))
      (node (ref "HI_MIN_ADDER") (pin "4") (pinfunction "E1_4") (pintype "output"))
      (node (ref "HI_MIN_AND") (pin "13") (pinfunction "4B_13") (pintype "input"))
    )
    (net (code "37") (name "Net-(HI_MIN_ADDER-A1)") (class "Default")
      (node (ref "HI_MIN_ADDER") (pin "5") (pinfunction "A1_5") (pintype "input"))
      (node (ref "HI_MIN_REG") (pin "12") (pinfunction "QD_12") (pintype "output"))
    )
    (net (code "38") (name "Net-(HI_MIN_ADDER-A4)") (class "Default")
      (node (ref "HI_MIN_ADDER") (pin "12") (pinfunction "A4_12") (pintype "input"))
      (node (ref "HI_MIN_REG") (pin "15") (pinfunction "QA_15") (pintype "output"))
      (node (ref "HR_REG") (pin "7") (pinfunction "SLSER_7") (pintype "input"))
    )
    (net (code "39") (name "Net-(HI_MIN_ADDER-B2)") (class "Default")
      (node (ref "HI_MIN_ADDER") (pin "2") (pinfunction "B2_2") (pintype "input"))
      (node (ref "HI_MIN_REG") (pin "13") (pinfunction "QC_13") (pintype "output"))
    )
    (net (code "40") (name "Net-(HI_MIN_ADDER-B3)") (class "Default")
      (node (ref "HI_MIN_ADDER") (pin "15") (pinfunction "B3_15") (pintype "input"))
      (node (ref "HI_MIN_REG") (pin "14") (pinfunction "QB_14") (pintype "output"))
    )
    (net (code "41") (name "Net-(HI_MIN_ADDER-C0)") (class "Default")
      (node (ref "HI_MIN_ADDER") (pin "7") (pinfunction "C0_7") (pintype "input"))
      (node (ref "SPLIT_ADDER") (pin "9") (pinfunction "C4_9") (pintype "input"))
    )
    (net (code "42") (name "Net-(HI_MIN_AND-1B)") (class "Default")
      (node (ref "HI_MIN_AND") (pin "10") (pinfunction "3B_10") (pintype "input"))
      (node (ref "HI_MIN_AND") (pin "12") (pinfunction "4A_12") (pintype "input"))
      (node (ref "HI_MIN_AND") (pin "2") (pinfunction "1B_2") (pintype "input"))
      (node (ref "HI_MIN_AND") (pin "4") (pinfunction "2A_4") (pintype "input"))
      (node (ref "NAND1") (pin "6") (pinfunction "2Y_6") (pintype "output"))
    )
    (net (code "43") (name "Net-(HI_MIN_AND-1Y)") (class "Default")
      (node (ref "HI_MIN_AND") (pin "3") (pinfunction "1Y_3") (pintype "output"))
      (node (ref "HI_MIN_REG") (pin "4") (pinfunction "B_4") (pintype "input"))
    )
    (net (code "44") (name "Net-(HI_MIN_AND-2Y)") (class "Default")
      (node (ref "HI_MIN_AND") (pin "6") (pinfunction "2Y_6") (pintype "output"))
      (node (ref "HI_MIN_REG") (pin "3") (pinfunction "A_3") (pintype "input"))
    )
    (net (code "45") (name "Net-(HI_MIN_AND-3Y)") (class "Default")
      (node (ref "HI_MIN_AND") (pin "8") (pinfunction "3Y_8") (pintype "output"))
      (node (ref "HI_MIN_REG") (pin "6") (pinfunction "D_6") (pintype "input"))
    )
    (net (code "46") (name "Net-(HI_MIN_AND-4Y)") (class "Default")
      (node (ref "HI_MIN_AND") (pin "11") (pinfunction "4Y_11") (pintype "output"))
      (node (ref "HI_MIN_REG") (pin "5") (pinfunction "C_5") (pintype "input"))
    )
    (net (code "47") (name "Net-(HI_MIN_REG-S0)") (class "Default")
      (node (ref "HI_MIN_REG") (pin "9") (pinfunction "S0_9") (pintype "input"))
      (node (ref "MUX2") (pin "7") (pinfunction "2Y_7") (pintype "output"))
    )
    (net (code "48") (name "Net-(HI_MIN_REG-S1)") (class "Default")
      (node (ref "HI_MIN_REG") (pin "10") (pinfunction "S1_10") (pintype "input"))
      (node (ref "MUX2") (pin "4") (pinfunction "1Y_4") (pintype "output"))
    )
    (net (code "49") (name "Net-(HI_MIN_REG-SRSER)") (class "Default")
      (node (ref "HI_MIN_REG") (pin "2") (pinfunction "SRSER_2") (pintype "input"))
      (node (ref "HR_ADDER") (pin "5") (pinfunction "A1_5") (pintype "input"))
      (node (ref "HR_REG") (pin "12") (pinfunction "QD_12") (pintype "output"))
    )
    (net (code "50") (name "Net-(HI_SEC_MUX-B)") (class "Default")
      (node (ref "HI_SEC_MUX") (pin "9") (pinfunction "B_9") (pintype "passive"))
      (node (ref "LO_MIN_MUX") (pin "9") (pinfunction "B_9") (pintype "passive"))
      (node (ref "MUX2") (pin "2") (pinfunction "1A_2") (pintype "input"))
      (node (ref "MUX2") (pin "5") (pinfunction "2A_5") (pintype "input"))
      (node (ref "NAND0") (pin "10") (pinfunction "3B_10") (pintype "input"))
      (node (ref "NAND0") (pin "9") (pinfunction "3A_9") (pintype "input"))
      (node (ref "OR1") (pin "3") (pinfunction "1Y_3") (pintype "output"))
    )
    (net (code "51") (name "Net-(HI_SEC_MUX-X)") (class "Default")
      (node (ref "HI_SEC_MUX") (pin "13") (pinfunction "X_13") (pintype "bidirectional"))
      (node (ref "SPLI_REG") (pin "5") (pinfunction "C_5") (pintype "input"))
    )
    (net (code "52") (name "Net-(HI_SEC_MUX-Y)") (class "Default")
      (node (ref "HI_SEC_MUX") (pin "3") (pinfunction "Y_3") (pintype "bidirectional"))
      (node (ref "SPLI_REG") (pin "6") (pinfunction "D_6") (pintype "input"))
    )
    (net (code "53") (name "Net-(HR_ADDER-A3)") (class "Default")
      (node (ref "HR_ADDER") (pin "11") (pinfunction "B4_11") (pintype "input"))
      (node (ref "HR_ADDER") (pin "14") (pinfunction "A3_14") (pintype "input"))
    )
    (net (code "54") (name "Net-(HR_ADDER-A4)") (class "Default")
      (node (ref "HR_ADDER") (pin "12") (pinfunction "A4_12") (pintype "input"))
      (node (ref "HR_REG") (pin "15") (pinfunction "QA_15") (pintype "output"))
    )
    (net (code "55") (name "Net-(HR_ADDER-B2)") (class "Default")
      (node (ref "HR_ADDER") (pin "2") (pinfunction "B2_2") (pintype "input"))
      (node (ref "HR_REG") (pin "13") (pinfunction "QC_13") (pintype "output"))
    )
    (net (code "56") (name "Net-(HR_ADDER-B3)") (class "Default")
      (node (ref "HR_ADDER") (pin "15") (pinfunction "B3_15") (pintype "input"))
      (node (ref "HR_REG") (pin "14") (pinfunction "QB_14") (pintype "output"))
    )
    (net (code "57") (name "Net-(HR_ADDER-E1)") (class "Default")
      (node (ref "HR_ADDER") (pin "4") (pinfunction "E1_4") (pintype "output"))
      (node (ref "HR_AND") (pin "13") (pinfunction "4B_13") (pintype "input"))
    )
    (net (code "58") (name "Net-(HR_ADDER-E2)") (class "Default")
      (node (ref "HR_ADDER") (pin "1") (pinfunction "E2_1") (pintype "output"))
      (node (ref "HR_AND") (pin "9") (pinfunction "3A_9") (pintype "input"))
      (node (ref "OR2") (pin "4") (pinfunction "2A_4") (pintype "input"))
    )
    (net (code "59") (name "Net-(HR_ADDER-E3)") (class "Default")
      (node (ref "HR_ADDER") (pin "13") (pinfunction "E3_13") (pintype "output"))
      (node (ref "HR_AND") (pin "1") (pinfunction "1A_1") (pintype "input"))
      (node (ref "OR2") (pin "5") (pinfunction "2B_5") (pintype "input"))
    )
    (net (code "60") (name "Net-(HR_AND-1B)") (class "Default")
      (node (ref "HR_AND") (pin "10") (pinfunction "3B_10") (pintype "input"))
      (node (ref "HR_AND") (pin "12") (pinfunction "4A_12") (pintype "input"))
      (node (ref "HR_AND") (pin "2") (pinfunction "1B_2") (pintype "input"))
      (node (ref "HR_AND") (pin "4") (pinfunction "2A_4") (pintype "input"))
      (node (ref "NAND1") (pin "3") (pinfunction "1Y_3") (pintype "output"))
    )
    (net (code "61") (name "Net-(HR_AND-1Y)") (class "Default")
      (node (ref "HR_AND") (pin "3") (pinfunction "1Y_3") (pintype "output"))
      (node (ref "HR_REG") (pin "4") (pinfunction "B_4") (pintype "input"))
    )
    (net (code "62") (name "Net-(HR_AND-2Y)") (class "Default")
      (node (ref "HR_AND") (pin "6") (pinfunction "2Y_6") (pintype "output"))
      (node (ref "HR_REG") (pin "3") (pinfunction "A_3") (pintype "input"))
    )
    (net (code "63") (name "Net-(HR_AND-3Y)") (class "Default")
      (node (ref "HR_AND") (pin "8") (pinfunction "3Y_8") (pintype "output"))
      (node (ref "HR_REG") (pin "6") (pinfunction "D_6") (pintype "input"))
    )
    (net (code "64") (name "Net-(HR_AND-4Y)") (class "Default")
      (node (ref "HR_AND") (pin "11") (pinfunction "4Y_11") (pintype "output"))
      (node (ref "HR_REG") (pin "5") (pinfunction "C_5") (pintype "input"))
    )
    (net (code "65") (name "Net-(HR_REG-S0)") (class "Default")
      (node (ref "HR_REG") (pin "9") (pinfunction "S0_9") (pintype "input"))
      (node (ref "MUX2") (pin "12") (pinfunction "4Y_12") (pintype "output"))
    )
    (net (code "66") (name "Net-(HR_REG-S1)") (class "Default")
      (node (ref "HR_REG") (pin "10") (pinfunction "S1_10") (pintype "input"))
      (node (ref "MUX2") (pin "9") (pinfunction "3Y_9") (pintype "output"))
    )
    (net (code "67") (name "Net-(JKFF0-1J)") (class "Default")
      (node (ref "JKFF0") (pin "2") (pinfunction "1J_2") (pintype "input"))
      (node (ref "NAND1") (pin "10") (pinfunction "3B_10") (pintype "input"))
      (node (ref "NAND1") (pin "9") (pinfunction "3A_9") (pintype "input"))
      (node (ref "OR2") (pin "3") (pinfunction "1Y_3") (pintype "output"))
    )
    (net (code "68") (name "Net-(JKFF0-~{1K})") (class "Default")
      (node (ref "JKFF0") (pin "3") (pinfunction "~{1K}_3") (pintype "input"))
      (node (ref "NAND1") (pin "8") (pinfunction "3Y_8") (pintype "output"))
    )
    (net (code "69") (name "Net-(LO_MIN_MUX-X)") (class "Default")
      (node (ref "LO_MIN_MUX") (pin "13") (pinfunction "X_13") (pintype "bidirectional"))
      (node (ref "SPLI_REG") (pin "4") (pinfunction "B_4") (pintype "input"))
    )
    (net (code "70") (name "Net-(LO_MIN_MUX-X1)") (class "Default")
      (node (ref "LO_MIN_MUX") (pin "14") (pinfunction "X1_14") (pintype "bidirectional"))
      (node (ref "SPLIT_ADDER") (pin "13") (pinfunction "E3_13") (pintype "output"))
    )
    (net (code "71") (name "Net-(LO_MIN_MUX-Y)") (class "Default")
      (node (ref "LO_MIN_MUX") (pin "3") (pinfunction "Y_3") (pintype "bidirectional"))
      (node (ref "SPLI_REG") (pin "3") (pinfunction "A_3") (pintype "input"))
    )
    (net (code "72") (name "Net-(LO_MIN_MUX-Y1)") (class "Default")
      (node (ref "LO_MIN_MUX") (pin "5") (pinfunction "Y1_5") (pintype "bidirectional"))
      (node (ref "SPLIT_ADDER") (pin "10") (pinfunction "E4_10") (pintype "output"))
    )
    (net (code "73") (name "Net-(LO_SEC_ADDER-A1)") (class "Default")
      (node (ref "LO_SEC_ADDER") (pin "5") (pinfunction "A1_5") (pintype "input"))
      (node (ref "LO_SEC_REG") (pin "12") (pinfunction "QD_12") (pintype "output"))
      (node (ref "MS_REG") (pin "2") (pinfunction "SRSER_2") (pintype "input"))
    )
    (net (code "74") (name "Net-(LO_SEC_ADDER-A3)") (class "Default")
      (node (ref "LO_SEC_ADDER") (pin "11") (pinfunction "B4_11") (pintype "input"))
      (node (ref "LO_SEC_ADDER") (pin "14") (pinfunction "A3_14") (pintype "input"))
    )
    (net (code "75") (name "Net-(LO_SEC_ADDER-A4)") (class "Default")
      (node (ref "LO_SEC_ADDER") (pin "12") (pinfunction "A4_12") (pintype "input"))
      (node (ref "LO_SEC_REG") (pin "15") (pinfunction "QA_15") (pintype "output"))
      (node (ref "SPLI_REG") (pin "7") (pinfunction "SLSER_7") (pintype "input"))
    )
    (net (code "76") (name "Net-(LO_SEC_ADDER-B2)") (class "Default")
      (node (ref "LO_SEC_ADDER") (pin "2") (pinfunction "B2_2") (pintype "input"))
      (node (ref "LO_SEC_REG") (pin "13") (pinfunction "QC_13") (pintype "output"))
    )
    (net (code "77") (name "Net-(LO_SEC_ADDER-B3)") (class "Default")
      (node (ref "LO_SEC_ADDER") (pin "15") (pinfunction "B3_15") (pintype "input"))
      (node (ref "LO_SEC_REG") (pin "14") (pinfunction "QB_14") (pintype "output"))
    )
    (net (code "78") (name "Net-(LO_SEC_ADDER-E1)") (class "Default")
      (node (ref "LO_SEC_ADDER") (pin "4") (pinfunction "E1_4") (pintype "output"))
      (node (ref "LO_SEC_AND") (pin "13") (pinfunction "4B_13") (pintype "input"))
    )
    (net (code "79") (name "Net-(LO_SEC_ADDER-E2)") (class "Default")
      (node (ref "LO_SEC_ADDER") (pin "1") (pinfunction "E2_1") (pintype "output"))
      (node (ref "LO_SEC_AND") (pin "9") (pinfunction "3A_9") (pintype "input"))
    )
    (net (code "80") (name "Net-(LO_SEC_AND-1B)") (class "Default")
      (node (ref "LO_SEC_AND") (pin "10") (pinfunction "3B_10") (pintype "input"))
      (node (ref "LO_SEC_AND") (pin "12") (pinfunction "4A_12") (pintype "input"))
      (node (ref "LO_SEC_AND") (pin "2") (pinfunction "1B_2") (pintype "input"))
      (node (ref "LO_SEC_AND") (pin "4") (pinfunction "2A_4") (pintype "input"))
      (node (ref "NAND0") (pin "8") (pinfunction "3Y_8") (pintype "output"))
    )
    (net (code "81") (name "Net-(LO_SEC_AND-1Y)") (class "Default")
      (node (ref "LO_SEC_AND") (pin "3") (pinfunction "1Y_3") (pintype "output"))
      (node (ref "LO_SEC_REG") (pin "4") (pinfunction "B_4") (pintype "input"))
    )
    (net (code "82") (name "Net-(LO_SEC_AND-2Y)") (class "Default")
      (node (ref "LO_SEC_AND") (pin "6") (pinfunction "2Y_6") (pintype "output"))
      (node (ref "LO_SEC_REG") (pin "3") (pinfunction "A_3") (pintype "input"))
    )
    (net (code "83") (name "Net-(LO_SEC_AND-3Y)") (class "Default")
      (node (ref "LO_SEC_AND") (pin "8") (pinfunction "3Y_8") (pintype "output"))
      (node (ref "LO_SEC_REG") (pin "6") (pinfunction "D_6") (pintype "input"))
    )
    (net (code "84") (name "Net-(LO_SEC_AND-4Y)") (class "Default")
      (node (ref "LO_SEC_AND") (pin "11") (pinfunction "4Y_11") (pintype "output"))
      (node (ref "LO_SEC_REG") (pin "5") (pinfunction "C_5") (pintype "input"))
    )
    (net (code "85") (name "Net-(LO_SEC_REG-S0)") (class "Default")
      (node (ref "LO_SEC_REG") (pin "9") (pinfunction "S0_9") (pintype "input"))
      (node (ref "MUX1") (pin "7") (pinfunction "2Y_7") (pintype "output"))
    )
    (net (code "86") (name "Net-(LO_SEC_REG-S1)") (class "Default")
      (node (ref "LO_SEC_REG") (pin "10") (pinfunction "S1_10") (pintype "input"))
      (node (ref "MUX1") (pin "4") (pinfunction "1Y_4") (pintype "output"))
    )
    (net (code "87") (name "Net-(LO_SEC_REG-SLSER)") (class "Default")
      (node (ref "LO_SEC_REG") (pin "7") (pinfunction "SLSER_7") (pintype "input"))
      (node (ref "MS_ADDER") (pin "12") (pinfunction "A4_12") (pintype "input"))
      (node (ref "MS_REG") (pin "15") (pinfunction "QA_15") (pintype "output"))
    )
    (net (code "88") (name "Net-(MS_ADDER-A1)") (class "Default")
      (node (ref "MS_ADDER") (pin "5") (pinfunction "A1_5") (pintype "input"))
      (node (ref "MS_REG") (pin "12") (pinfunction "QD_12") (pintype "output"))
    )
    (net (code "89") (name "Net-(MS_ADDER-B2)") (class "Default")
      (node (ref "MS_ADDER") (pin "2") (pinfunction "B2_2") (pintype "input"))
      (node (ref "MS_REG") (pin "13") (pinfunction "QC_13") (pintype "output"))
    )
    (net (code "90") (name "Net-(MS_ADDER-B3)") (class "Default")
      (node (ref "MS_ADDER") (pin "15") (pinfunction "B3_15") (pintype "input"))
      (node (ref "MS_REG") (pin "14") (pinfunction "QB_14") (pintype "output"))
    )
    (net (code "91") (name "Net-(MS_ADDER-E1)") (class "Default")
      (node (ref "MS_ADDER") (pin "4") (pinfunction "E1_4") (pintype "output"))
      (node (ref "MS_AND") (pin "9") (pinfunction "3A_9") (pintype "input"))
      (node (ref "OR0") (pin "13") (pinfunction "4B_13") (pintype "input"))
    )
    (net (code "92") (name "Net-(MS_ADDER-E2)") (class "Default")
      (node (ref "MS_ADDER") (pin "1") (pinfunction "E2_1") (pintype "output"))
      (node (ref "MS_AND") (pin "13") (pinfunction "4B_13") (pintype "input"))
    )
    (net (code "93") (name "Net-(MS_ADDER-E3)") (class "Default")
      (node (ref "MS_ADDER") (pin "13") (pinfunction "E3_13") (pintype "output"))
      (node (ref "MS_AND") (pin "1") (pinfunction "1A_1") (pintype "input"))
      (node (ref "OR0") (pin "12") (pinfunction "4A_12") (pintype "input"))
    )
    (net (code "94") (name "Net-(MS_ADDER-E4)") (class "Default")
      (node (ref "MS_ADDER") (pin "10") (pinfunction "E4_10") (pintype "output"))
      (node (ref "MS_AND") (pin "5") (pinfunction "2B_5") (pintype "input"))
      (node (ref "NAND0") (pin "1") (pinfunction "1A_1") (pintype "input"))
    )
    (net (code "95") (name "Net-(MS_AND-1B)") (class "Default")
      (node (ref "MS_AND") (pin "10") (pinfunction "3B_10") (pintype "input"))
      (node (ref "MS_AND") (pin "12") (pinfunction "4A_12") (pintype "input"))
      (node (ref "MS_AND") (pin "2") (pinfunction "1B_2") (pintype "input"))
      (node (ref "MS_AND") (pin "4") (pinfunction "2A_4") (pintype "input"))
      (node (ref "NAND0") (pin "6") (pinfunction "2Y_6") (pintype "output"))
    )
    (net (code "96") (name "Net-(MS_AND-1Y)") (class "Default")
      (node (ref "MS_AND") (pin "3") (pinfunction "1Y_3") (pintype "output"))
      (node (ref "MS_REG") (pin "4") (pinfunction "B_4") (pintype "input"))
    )
    (net (code "97") (name "Net-(MS_AND-2Y)") (class "Default")
      (node (ref "MS_AND") (pin "6") (pinfunction "2Y_6") (pintype "output"))
      (node (ref "MS_REG") (pin "3") (pinfunction "A_3") (pintype "input"))
    )
    (net (code "98") (name "Net-(MS_AND-3Y)") (class "Default")
      (node (ref "MS_AND") (pin "8") (pinfunction "3Y_8") (pintype "output"))
      (node (ref "MS_REG") (pin "6") (pinfunction "D_6") (pintype "input"))
    )
    (net (code "99") (name "Net-(MS_AND-4Y)") (class "Default")
      (node (ref "MS_AND") (pin "11") (pinfunction "4Y_11") (pintype "output"))
      (node (ref "MS_REG") (pin "5") (pinfunction "C_5") (pintype "input"))
    )
    (net (code "100") (name "Net-(MUX1-1B)") (class "Default")
      (node (ref "MUX1") (pin "10") (pinfunction "3B_10") (pintype "input"))
      (node (ref "MUX1") (pin "3") (pinfunction "1B_3") (pintype "input"))
      (node (ref "OR0") (pin "3") (pinfunction "1Y_3") (pintype "output"))
    )
    (net (code "101") (name "Net-(MUX1-2B)") (class "Default")
      (node (ref "MUX1") (pin "13") (pinfunction "4B_13") (pintype "input"))
      (node (ref "MUX1") (pin "6") (pinfunction "2B_6") (pintype "input"))
      (node (ref "OR0") (pin "8") (pinfunction "3Y_8") (pintype "output"))
    )
    (net (code "102") (name "Net-(MUX1-3A)") (class "Default")
      (node (ref "MUX1") (pin "11") (pinfunction "3A_11") (pintype "input"))
      (node (ref "MUX1") (pin "14") (pinfunction "4A_14") (pintype "input"))
    )
    (net (code "103") (name "Net-(MUX1-3Y)") (class "Default")
      (node (ref "MUX1") (pin "9") (pinfunction "3Y_9") (pintype "output"))
      (node (ref "SPLI_REG") (pin "10") (pinfunction "S1_10") (pintype "input"))
    )
    (net (code "104") (name "Net-(MUX1-4Y)") (class "Default")
      (node (ref "MUX1") (pin "12") (pinfunction "4Y_12") (pintype "output"))
      (node (ref "SPLI_REG") (pin "9") (pinfunction "S0_9") (pintype "input"))
    )
    (net (code "105") (name "Net-(MUX2-1B)") (class "Default")
      (node (ref "MUX2") (pin "3") (pinfunction "1B_3") (pintype "input"))
      (node (ref "OR1") (pin "8") (pinfunction "3Y_8") (pintype "output"))
    )
    (net (code "106") (name "Net-(MUX2-2B)") (class "Default")
      (node (ref "MUX2") (pin "6") (pinfunction "2B_6") (pintype "input"))
      (node (ref "OR1") (pin "11") (pinfunction "4Y_11") (pintype "output"))
    )
    (net (code "107") (name "Net-(MUX2-3B)") (class "Default")
      (node (ref "MUX2") (pin "10") (pinfunction "3B_10") (pintype "input"))
      (node (ref "OR2") (pin "8") (pinfunction "3Y_8") (pintype "output"))
    )
    (net (code "108") (name "Net-(MUX2-4B)") (class "Default")
      (node (ref "MUX2") (pin "13") (pinfunction "4B_13") (pintype "input"))
      (node (ref "OR2") (pin "11") (pinfunction "4Y_11") (pintype "output"))
    )
    (net (code "109") (name "Net-(NAND0-1B)") (class "Default")
      (node (ref "NAND0") (pin "2") (pinfunction "1B_2") (pintype "input"))
      (node (ref "OR0") (pin "11") (pinfunction "4Y_11") (pintype "output"))
    )
    (net (code "110") (name "Net-(NAND0-1Y)") (class "Default")
      (node (ref "NAND0") (pin "12") (pinfunction "4A_12") (pintype "input"))
      (node (ref "NAND0") (pin "13") (pinfunction "4B_13") (pintype "input"))
      (node (ref "NAND0") (pin "3") (pinfunction "1Y_3") (pintype "output"))
      (node (ref "NAND0") (pin "4") (pinfunction "2A_4") (pintype "input"))
    )
    (net (code "111") (name "Net-(OR1-1B)") (class "Default")
      (node (ref "OR1") (pin "13") (pinfunction "4B_13") (pintype "input"))
      (node (ref "OR1") (pin "2") (pinfunction "1B_2") (pintype "input"))
      (node (ref "OR1") (pin "6") (pinfunction "2Y_6") (pintype "output"))
      (node (ref "OR1") (pin "9") (pinfunction "3A_9") (pintype "input"))
    )
    (net (code "112") (name "unconnected-(AND1-4A-Pad12)") (class "Default")
      (node (ref "AND1") (pin "12") (pinfunction "4A_12") (pintype "input"))
    )
    (net (code "113") (name "unconnected-(AND1-4B-Pad13)") (class "Default")
      (node (ref "AND1") (pin "13") (pinfunction "4B_13") (pintype "input"))
    )
    (net (code "114") (name "unconnected-(AND1-4Y-Pad11)") (class "Default")
      (node (ref "AND1") (pin "11") (pinfunction "4Y_11") (pintype "output"))
    )
    (net (code "115") (name "unconnected-(HI_MIN_ADDER-C4-Pad9)") (class "Default")
      (node (ref "HI_MIN_ADDER") (pin "9") (pinfunction "C4_9") (pintype "input"))
    )
    (net (code "116") (name "unconnected-(HR_ADDER-C4-Pad9)") (class "Default")
      (node (ref "HR_ADDER") (pin "9") (pinfunction "C4_9") (pintype "input"))
    )
    (net (code "117") (name "unconnected-(JKFF0-1Q-Pad6)") (class "Default")
      (node (ref "JKFF0") (pin "6") (pinfunction "1Q_6") (pintype "output"))
    )
    (net (code "118") (name "unconnected-(JKFF0-2CLK-Pad12)") (class "Default")
      (node (ref "JKFF0") (pin "12") (pinfunction "2CLK_12") (pintype "input"))
    )
    (net (code "119") (name "unconnected-(JKFF0-2J-Pad14)") (class "Default")
      (node (ref "JKFF0") (pin "14") (pinfunction "2J_14") (pintype "input"))
    )
    (net (code "120") (name "unconnected-(JKFF0-2Q-Pad10)") (class "Default")
      (node (ref "JKFF0") (pin "10") (pinfunction "2Q_10") (pintype "output"))
    )
    (net (code "121") (name "unconnected-(JKFF0-~{1Q}-Pad7)") (class "Default")
      (node (ref "JKFF0") (pin "7") (pinfunction "~{1Q}_7") (pintype "output"))
    )
    (net (code "122") (name "unconnected-(JKFF0-~{2CLR}-Pad15)") (class "Default")
      (node (ref "JKFF0") (pin "15") (pinfunction "~{2CLR}_15") (pintype "input"))
    )
    (net (code "123") (name "unconnected-(JKFF0-~{2K}-Pad13)") (class "Default")
      (node (ref "JKFF0") (pin "13") (pinfunction "~{2K}_13") (pintype "input"))
    )
    (net (code "124") (name "unconnected-(JKFF0-~{2PRE}-Pad11)") (class "Default")
      (node (ref "JKFF0") (pin "11") (pinfunction "~{2PRE}_11") (pintype "input"))
    )
    (net (code "125") (name "unconnected-(JKFF0-~{2Q}-Pad9)") (class "Default")
      (node (ref "JKFF0") (pin "9") (pinfunction "~{2Q}_9") (pintype "output"))
    )
    (net (code "126") (name "unconnected-(MS_ADDER-C4-Pad9)") (class "Default")
      (node (ref "MS_ADDER") (pin "9") (pinfunction "C4_9") (pintype "input"))
    )
    (net (code "127") (name "unconnected-(MUX1-~{G}-Pad15)") (class "Default")
      (node (ref "MUX1") (pin "15") (pinfunction "~{G}_15") (pintype "input"))
    )
    (net (code "128") (name "unconnected-(NAND1-4A-Pad12)") (class "Default")
      (node (ref "NAND1") (pin "12") (pinfunction "4A_12") (pintype "input"))
    )
    (net (code "129") (name "unconnected-(NAND1-4B-Pad13)") (class "Default")
      (node (ref "NAND1") (pin "13") (pinfunction "4B_13") (pintype "input"))
    )
    (net (code "130") (name "unconnected-(NAND1-4Y-Pad11)") (class "Default")
      (node (ref "NAND1") (pin "11") (pinfunction "4Y_11") (pintype "output"))
    )
    (net (code "131") (name "unconnected-(OR0-2A-Pad4)") (class "Default")
      (node (ref "OR0") (pin "4") (pinfunction "2A_4") (pintype "input"))
    )
    (net (code "132") (name "unconnected-(OR0-2B-Pad5)") (class "Default")
      (node (ref "OR0") (pin "5") (pinfunction "2B_5") (pintype "input"))
    )
    (net (code "133") (name "unconnected-(OR0-2Y-Pad6)") (class "Default")
      (node (ref "OR0") (pin "6") (pinfunction "2Y_6") (pintype "output"))
    )
    (net (code "134") (name "unconnected-(SPLI_REG-SRSER-Pad2)") (class "Default")
      (node (ref "SPLI_REG") (pin "2") (pinfunction "SRSER_2") (pintype "input"))
    )
    (net (code "135") (name "unconnected-(U1-1Q-Pad6)") (class "Default")
      (node (ref "U1") (pin "6") (pinfunction "1Q_6") (pintype "output"))
    )
    (net (code "136") (name "unconnected-(U1-2J-Pad14)") (class "Default")
      (node (ref "U1") (pin "14") (pinfunction "2J_14") (pintype "input"))
    )
    (net (code "137") (name "unconnected-(U1-2Q-Pad10)") (class "Default")
      (node (ref "U1") (pin "10") (pinfunction "2Q_10") (pintype "output"))
    )
    (net (code "138") (name "unconnected-(U1-~{1Q}-Pad7)") (class "Default")
      (node (ref "U1") (pin "7") (pinfunction "~{1Q}_7") (pintype "output"))
    )
    (net (code "139") (name "unconnected-(U1-~{2K}-Pad13)") (class "Default")
      (node (ref "U1") (pin "13") (pinfunction "~{2K}_13") (pintype "input"))
    )
    (net (code "140") (name "unconnected-(U1-~{2Q}-Pad9)") (class "Default")
      (node (ref "U1") (pin "9") (pinfunction "~{2Q}_9") (pintype "output"))
    )
    (net (code "141") (name "unconnected-(U2-1A-Pad1)") (class "Default")
      (node (ref "U2") (pin "1") (pinfunction "1A_1") (pintype "input"))
    )
    (net (code "142") (name "unconnected-(U2-1B-Pad2)") (class "Default")
      (node (ref "U2") (pin "2") (pinfunction "1B_2") (pintype "input"))
    )
    (net (code "143") (name "unconnected-(U2-1Y-Pad3)") (class "Default")
      (node (ref "U2") (pin "3") (pinfunction "1Y_3") (pintype "output"))
    )
    (net (code "144") (name "unconnected-(U2-2A-Pad4)") (class "Default")
      (node (ref "U2") (pin "4") (pinfunction "2A_4") (pintype "input"))
    )
    (net (code "145") (name "unconnected-(U2-2B-Pad5)") (class "Default")
      (node (ref "U2") (pin "5") (pinfunction "2B_5") (pintype "input"))
    )
    (net (code "146") (name "unconnected-(U2-2Y-Pad6)") (class "Default")
      (node (ref "U2") (pin "6") (pinfunction "2Y_6") (pintype "output"))
    )
    (net (code "147") (name "unconnected-(U2-3A-Pad9)") (class "Default")
      (node (ref "U2") (pin "9") (pinfunction "3A_9") (pintype "input"))
    )
    (net (code "148") (name "unconnected-(U2-3B-Pad10)") (class "Default")
      (node (ref "U2") (pin "10") (pinfunction "3B_10") (pintype "input"))
    )
    (net (code "149") (name "unconnected-(U2-3Y-Pad8)") (class "Default")
      (node (ref "U2") (pin "8") (pinfunction "3Y_8") (pintype "output"))
    )
    (net (code "150") (name "unconnected-(U2-4A-Pad12)") (class "Default")
      (node (ref "U2") (pin "12") (pinfunction "4A_12") (pintype "input"))
    )
    (net (code "151") (name "unconnected-(U2-4B-Pad13)") (class "Default")
      (node (ref "U2") (pin "13") (pinfunction "4B_13") (pintype "input"))
    )
    (net (code "152") (name "unconnected-(U2-4Y-Pad11)") (class "Default")
      (node (ref "U2") (pin "11") (pinfunction "4Y_11") (pintype "output"))
    )
  )
)
